# design.net
KiCad netlist of a schematic drawn in Altium Designer
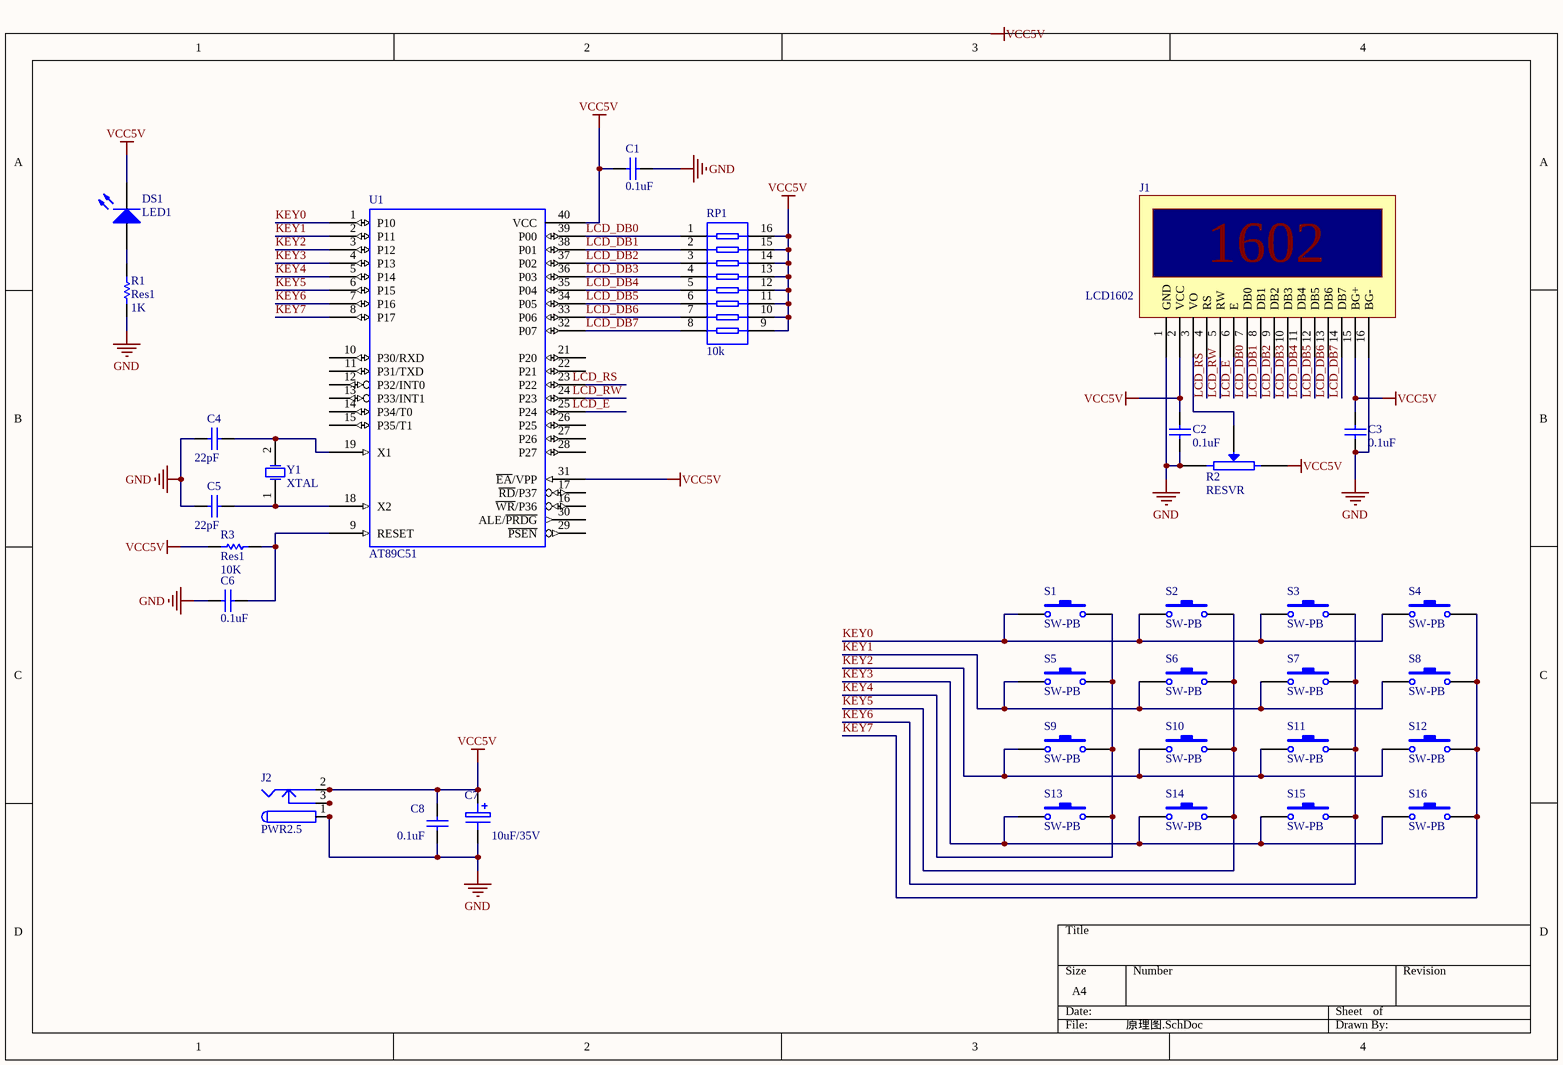
[diagram p0: 原理图.SchDoc]

(export (version "E")
  (design (tool "Eeschema 10.0.6"))
  (components
    (comp (ref "C1")
      (value "0.1uF")
      (footprint "RAD-0.3")
      (description "Capacitor")
      (fields (field (name "Comment") "Cap") (field (name "PUBLISHER") "Altium Limited"))
      (libsource (lib "Miscellaneous Devices") (part "Cap"))
    )
    (comp (ref "C2")
      (value "0.1uF")
      (footprint "RAD-0.3")
      (description "Capacitor")
      (fields (field (name "Comment") "Cap") (field (name "PUBLISHER") "Altium Limited"))
      (libsource (lib "Miscellaneous Devices") (part "Cap"))
    )
    (comp (ref "C3")
      (value "0.1uF")
      (footprint "RAD-0.3")
      (description "Capacitor")
      (fields (field (name "Comment") "Cap") (field (name "PUBLISHER") "Altium Limited"))
      (libsource (lib "Miscellaneous Devices") (part "Cap"))
    )
    (comp (ref "C4")
      (value "22pF")
      (footprint "RAD-0.3")
      (description "Capacitor")
      (fields (field (name "Comment") "Cap") (field (name "PUBLISHER") "Altium Limited"))
      (libsource (lib "Miscellaneous Devices") (part "Cap"))
    )
    (comp (ref "C5")
      (value "22pF")
      (footprint "RAD-0.3")
      (description "Capacitor")
      (fields (field (name "Comment") "Cap") (field (name "PUBLISHER") "Altium Limited"))
      (libsource (lib "Miscellaneous Devices") (part "Cap"))
    )
    (comp (ref "C6")
      (value "0.1uF")
      (footprint "RAD-0.3")
      (description "Capacitor")
      (fields (field (name "Comment") "Cap") (field (name "PUBLISHER") "Altium Limited"))
      (libsource (lib "Miscellaneous Devices") (part "Cap"))
    )
    (comp (ref "C7") (value "10uF/35V") (footprint "RB.1/.2") (libsource (lib "电容") (part "EC")))
    (comp (ref "C8")
      (value "0.1uF")
      (footprint "RAD-0.3")
      (description "Capacitor")
      (fields (field (name "Comment") "Cap") (field (name "PUBLISHER") "Altium Limited"))
      (libsource (lib "Miscellaneous Devices") (part "Cap"))
    )
    (comp (ref "DS1")
      (value "LED1")
      (footprint "LED-1")
      (description "Typical RED GaAs LED")
      (fields (field (name "PUBLISHER") "Altium Limited"))
      (libsource (lib "Miscellaneous Devices") (part "LED1"))
    )
    (comp (ref "J1") (value "LCD1602") (libsource (lib "常用元件库") (part "LCD1602")))
    (comp (ref "J2")
      (value "PWR2.5")
      (footprint "KLD-0202")
      (description "Low Voltage Power Supply Connector")
      (fields (field (name "PUBLISHER") "Altium Limited"))
      (libsource (lib "Miscellaneous Connectors") (part "PWR2.5"))
    )
    (comp (ref "R1")
      (value "Res1")
      (footprint "AXIAL-0.3")
      (description "Resistor")
      (fields (field (name "ALTIUM_VALUE") "1K") (field (name "PUBLISHER") "Altium Limited"))
      (libsource (lib "Miscellaneous Devices") (part "Res1"))
    )
    (comp (ref "R2")
      (value "RESVR")
      (footprint "VR")
      (description "Potentiometer")
      (libsource (lib "电阻") (part "RESVR"))
    )
    (comp (ref "R3")
      (value "Res1")
      (footprint "AXIAL-0.3")
      (description "Resistor")
      (fields (field (name "ALTIUM_VALUE") "10K") (field (name "PUBLISHER") "Altium Limited"))
      (libsource (lib "Miscellaneous Devices") (part "Res1"))
    )
    (comp (ref "RP1") (value "10k") (footprint "DIP16") (libsource (lib "电阻") (part "RESPACK4")))
    (comp (ref "S1")
      (value "SW-PB")
      (footprint "SPST-2")
      (description "Switch")
      (fields (field (name "PUBLISHER") "Altium Limited"))
      (libsource (lib "Miscellaneous Devices") (part "SW-PB"))
    )
    (comp (ref "S2")
      (value "SW-PB")
      (footprint "SPST-2")
      (description "Switch")
      (fields (field (name "PUBLISHER") "Altium Limited"))
      (libsource (lib "Miscellaneous Devices") (part "SW-PB"))
    )
    (comp (ref "S3")
      (value "SW-PB")
      (footprint "SPST-2")
      (description "Switch")
      (fields (field (name "PUBLISHER") "Altium Limited"))
      (libsource (lib "Miscellaneous Devices") (part "SW-PB"))
    )
    (comp (ref "S4")
      (value "SW-PB")
      (footprint "SPST-2")
      (description "Switch")
      (fields (field (name "PUBLISHER") "Altium Limited"))
      (libsource (lib "Miscellaneous Devices") (part "SW-PB"))
    )
    (comp (ref "S5")
      (value "SW-PB")
      (footprint "SPST-2")
      (description "Switch")
      (fields (field (name "PUBLISHER") "Altium Limited"))
      (libsource (lib "Miscellaneous Devices") (part "SW-PB"))
    )
    (comp (ref "S6")
      (value "SW-PB")
      (footprint "SPST-2")
      (description "Switch")
      (fields (field (name "PUBLISHER") "Altium Limited"))
      (libsource (lib "Miscellaneous Devices") (part "SW-PB"))
    )
    (comp (ref "S7")
      (value "SW-PB")
      (footprint "SPST-2")
      (description "Switch")
      (fields (field (name "PUBLISHER") "Altium Limited"))
      (libsource (lib "Miscellaneous Devices") (part "SW-PB"))
    )
    (comp (ref "S8")
      (value "SW-PB")
      (footprint "SPST-2")
      (description "Switch")
      (fields (field (name "PUBLISHER") "Altium Limited"))
      (libsource (lib "Miscellaneous Devices") (part "SW-PB"))
    )
    (comp (ref "S9")
      (value "SW-PB")
      (footprint "SPST-2")
      (description "Switch")
      (fields (field (name "PUBLISHER") "Altium Limited"))
      (libsource (lib "Miscellaneous Devices") (part "SW-PB"))
    )
    (comp (ref "S10")
      (value "SW-PB")
      (footprint "SPST-2")
      (description "Switch")
      (fields (field (name "PUBLISHER") "Altium Limited"))
      (libsource (lib "Miscellaneous Devices") (part "SW-PB"))
    )
    (comp (ref "S11")
      (value "SW-PB")
      (footprint "SPST-2")
      (description "Switch")
      (fields (field (name "PUBLISHER") "Altium Limited"))
      (libsource (lib "Miscellaneous Devices") (part "SW-PB"))
    )
    (comp (ref "S12")
      (value "SW-PB")
      (footprint "SPST-2")
      (description "Switch")
      (fields (field (name "PUBLISHER") "Altium Limited"))
      (libsource (lib "Miscellaneous Devices") (part "SW-PB"))
    )
    (comp (ref "S13")
      (value "SW-PB")
      (footprint "SPST-2")
      (description "Switch")
      (fields (field (name "PUBLISHER") "Altium Limited"))
      (libsource (lib "Miscellaneous Devices") (part "SW-PB"))
    )
    (comp (ref "S14")
      (value "SW-PB")
      (footprint "SPST-2")
      (description "Switch")
      (fields (field (name "PUBLISHER") "Altium Limited"))
      (libsource (lib "Miscellaneous Devices") (part "SW-PB"))
    )
    (comp (ref "S15")
      (value "SW-PB")
      (footprint "SPST-2")
      (description "Switch")
      (fields (field (name "PUBLISHER") "Altium Limited"))
      (libsource (lib "Miscellaneous Devices") (part "SW-PB"))
    )
    (comp (ref "S16")
      (value "SW-PB")
      (footprint "SPST-2")
      (description "Switch")
      (fields (field (name "PUBLISHER") "Altium Limited"))
      (libsource (lib "Miscellaneous Devices") (part "SW-PB"))
    )
    (comp (ref "U1") (value "AT89C51") (footprint "DIP-40") (libsource (lib "单片机及相关") (part "AT89C51")))
    (comp (ref "Y1")
      (value "XTAL")
      (footprint "BCY-W2/D3.1")
      (description "Crystal Oscillator")
      (fields (field (name "PUBLISHER") "Altium Limited"))
      (libsource (lib "Miscellaneous Devices") (part "XTAL"))
    )
  )
  (nets
    (net (code "1") (name "/KEY0") (class "Default")
      (node (ref "S1") (pin "1") (pinfunction "1_1") (pintype "passive"))
      (node (ref "S2") (pin "1") (pinfunction "1_1") (pintype "passive"))
      (node (ref "S3") (pin "1") (pinfunction "1_1") (pintype "passive"))
      (node (ref "S4") (pin "1") (pinfunction "1_1") (pintype "passive"))
      (node (ref "U1") (pin "1") (pinfunction "P10_1") (pintype "bidirectional"))
    )
    (net (code "2") (name "/KEY1") (class "Default")
      (node (ref "S5") (pin "1") (pinfunction "1_1") (pintype "passive"))
      (node (ref "S6") (pin "1") (pinfunction "1_1") (pintype "passive"))
      (node (ref "S7") (pin "1") (pinfunction "1_1") (pintype "passive"))
      (node (ref "S8") (pin "1") (pinfunction "1_1") (pintype "passive"))
      (node (ref "U1") (pin "2") (pinfunction "P11_2") (pintype "bidirectional"))
    )
    (net (code "3") (name "/KEY2") (class "Default")
      (node (ref "S10") (pin "1") (pinfunction "1_1") (pintype "passive"))
      (node (ref "S11") (pin "1") (pinfunction "1_1") (pintype "passive"))
      (node (ref "S12") (pin "1") (pinfunction "1_1") (pintype "passive"))
      (node (ref "S9") (pin "1") (pinfunction "1_1") (pintype "passive"))
      (node (ref "U1") (pin "3") (pinfunction "P12_3") (pintype "bidirectional"))
    )
    (net (code "4") (name "/KEY3") (class "Default")
      (node (ref "S13") (pin "1") (pinfunction "1_1") (pintype "passive"))
      (node (ref "S14") (pin "1") (pinfunction "1_1") (pintype "passive"))
      (node (ref "S15") (pin "1") (pinfunction "1_1") (pintype "passive"))
      (node (ref "S16") (pin "1") (pinfunction "1_1") (pintype "passive"))
      (node (ref "U1") (pin "4") (pinfunction "P13_4") (pintype "bidirectional"))
    )
    (net (code "5") (name "/KEY4") (class "Default")
      (node (ref "S1") (pin "2") (pinfunction "2_2") (pintype "passive"))
      (node (ref "S13") (pin "2") (pinfunction "2_2") (pintype "passive"))
      (node (ref "S5") (pin "2") (pinfunction "2_2") (pintype "passive"))
      (node (ref "S9") (pin "2") (pinfunction "2_2") (pintype "passive"))
      (node (ref "U1") (pin "5") (pinfunction "P14_5") (pintype "bidirectional"))
    )
    (net (code "6") (name "/KEY5") (class "Default")
      (node (ref "S10") (pin "2") (pinfunction "2_2") (pintype "passive"))
      (node (ref "S14") (pin "2") (pinfunction "2_2") (pintype "passive"))
      (node (ref "S2") (pin "2") (pinfunction "2_2") (pintype "passive"))
      (node (ref "S6") (pin "2") (pinfunction "2_2") (pintype "passive"))
      (node (ref "U1") (pin "6") (pinfunction "P15_6") (pintype "bidirectional"))
    )
    (net (code "7") (name "/KEY6") (class "Default")
      (node (ref "S11") (pin "2") (pinfunction "2_2") (pintype "passive"))
      (node (ref "S15") (pin "2") (pinfunction "2_2") (pintype "passive"))
      (node (ref "S3") (pin "2") (pinfunction "2_2") (pintype "passive"))
      (node (ref "S7") (pin "2") (pinfunction "2_2") (pintype "passive"))
      (node (ref "U1") (pin "7") (pinfunction "P16_7") (pintype "bidirectional"))
    )
    (net (code "8") (name "/KEY7") (class "Default")
      (node (ref "S12") (pin "2") (pinfunction "2_2") (pintype "passive"))
      (node (ref "S16") (pin "2") (pinfunction "2_2") (pintype "passive"))
      (node (ref "S4") (pin "2") (pinfunction "2_2") (pintype "passive"))
      (node (ref "S8") (pin "2") (pinfunction "2_2") (pintype "passive"))
      (node (ref "U1") (pin "8") (pinfunction "P17_8") (pintype "bidirectional"))
    )
    (net (code "9") (name "/LCD_DB0") (class "Default")
      (node (ref "J1") (pin "7") (pinfunction "DB0_7") (pintype "passive"))
      (node (ref "RP1") (pin "1") (pinfunction "1_1") (pintype "passive"))
      (node (ref "U1") (pin "39") (pinfunction "P00_39") (pintype "bidirectional"))
    )
    (net (code "10") (name "/LCD_DB1") (class "Default")
      (node (ref "J1") (pin "8") (pinfunction "DB1_8") (pintype "passive"))
      (node (ref "RP1") (pin "2") (pinfunction "2_2") (pintype "passive"))
      (node (ref "U1") (pin "38") (pinfunction "P01_38") (pintype "bidirectional"))
    )
    (net (code "11") (name "/LCD_DB2") (class "Default")
      (node (ref "J1") (pin "9") (pinfunction "DB2_9") (pintype "passive"))
      (node (ref "RP1") (pin "3") (pinfunction "3_3") (pintype "passive"))
      (node (ref "U1") (pin "37") (pinfunction "P02_37") (pintype "bidirectional"))
    )
    (net (code "12") (name "/LCD_DB3") (class "Default")
      (node (ref "J1") (pin "10") (pinfunction "DB3_10") (pintype "passive"))
      (node (ref "RP1") (pin "4") (pinfunction "4_4") (pintype "passive"))
      (node (ref "U1") (pin "36") (pinfunction "P03_36") (pintype "bidirectional"))
    )
    (net (code "13") (name "/LCD_DB4") (class "Default")
      (node (ref "J1") (pin "11") (pinfunction "DB4_11") (pintype "passive"))
      (node (ref "RP1") (pin "5") (pinfunction "5_5") (pintype "passive"))
      (node (ref "U1") (pin "35") (pinfunction "P04_35") (pintype "bidirectional"))
    )
    (net (code "14") (name "/LCD_DB5") (class "Default")
      (node (ref "J1") (pin "12") (pinfunction "DB5_12") (pintype "passive"))
      (node (ref "RP1") (pin "6") (pinfunction "6_6") (pintype "passive"))
      (node (ref "U1") (pin "34") (pinfunction "P05_34") (pintype "bidirectional"))
    )
    (net (code "15") (name "/LCD_DB6") (class "Default")
      (node (ref "J1") (pin "13") (pinfunction "DB6_13") (pintype "passive"))
      (node (ref "RP1") (pin "7") (pinfunction "7_7") (pintype "passive"))
      (node (ref "U1") (pin "33") (pinfunction "P06_33") (pintype "bidirectional"))
    )
    (net (code "16") (name "/LCD_DB7") (class "Default")
      (node (ref "J1") (pin "14") (pinfunction "DB7_14") (pintype "passive"))
      (node (ref "RP1") (pin "8") (pinfunction "8_8") (pintype "passive"))
      (node (ref "U1") (pin "32") (pinfunction "P07_32") (pintype "bidirectional"))
    )
    (net (code "17") (name "/LCD_E") (class "Default")
      (node (ref "J1") (pin "6") (pinfunction "E_6") (pintype "passive"))
    )
    (net (code "18") (name "/LCD_RS") (class "Default")
      (node (ref "J1") (pin "4") (pinfunction "RS_4") (pintype "passive"))
    )
    (net (code "19") (name "/LCD_RW") (class "Default")
      (node (ref "J1") (pin "5") (pinfunction "RW_5") (pintype "passive"))
    )
    (net (code "20") (name "GND") (class "Default")
      (node (ref "C1") (pin "1") (pinfunction "1_1") (pintype "passive"))
      (node (ref "C2") (pin "2") (pinfunction "2_2") (pintype "passive"))
      (node (ref "C3") (pin "2") (pinfunction "2_2") (pintype "passive"))
      (node (ref "C4") (pin "1") (pinfunction "1_1") (pintype "passive"))
      (node (ref "C5") (pin "1") (pinfunction "1_1") (pintype "passive"))
      (node (ref "C6") (pin "2") (pinfunction "2_2") (pintype "passive"))
      (node (ref "C7") (pin "2") (pinfunction "E_2") (pintype "passive"))
      (node (ref "C8") (pin "2") (pinfunction "2_2") (pintype "passive"))
      (node (ref "J1") (pin "1") (pinfunction "GND_1") (pintype "passive"))
      (node (ref "J1") (pin "16") (pinfunction "BG-_16") (pintype "passive"))
      (node (ref "J2") (pin "1") (pinfunction "1_1") (pintype "power_in"))
      (node (ref "J2") (pin "1A") (pinfunction "1A_1A") (pintype "power_in"))
      (node (ref "J2") (pin "1B") (pinfunction "1B_1B") (pintype "power_in"))
      (node (ref "R1") (pin "1") (pinfunction "1_1") (pintype "passive"))
      (node (ref "R2") (pin "1") (pinfunction "1_1") (pintype "passive"))
      (node (ref "U1") (pin "20") (pinfunction "GND_20") (pintype "power_in"))
    )
    (net (code "21") (name "Net-(DS1-A)") (class "Default")
      (node (ref "DS1") (pin "1") (pinfunction "A_1") (pintype "passive"))
      (node (ref "R1") (pin "2") (pinfunction "2_2") (pintype "passive"))
    )
    (net (code "22") (name "Net-(J1-VO)") (class "Default")
      (node (ref "J1") (pin "3") (pinfunction "VO_3") (pintype "passive"))
      (node (ref "R2") (pin "3") (pinfunction "W_3") (pintype "passive"))
    )
    (net (code "23") (name "Net-(J2-Pad3)") (class "Default")
      (node (ref "J2") (pin "3") (pinfunction "3_3") (pintype "power_in"))
      (node (ref "J2") (pin "3A") (pinfunction "3A_3A") (pintype "power_in"))
      (node (ref "J2") (pin "3B") (pinfunction "3B_3B") (pintype "power_in"))
    )
    (net (code "24") (name "Net-(U1-RESET)") (class "Default")
      (node (ref "C6") (pin "1") (pinfunction "1_1") (pintype "passive"))
      (node (ref "R3") (pin "2") (pinfunction "2_2") (pintype "passive"))
      (node (ref "U1") (pin "9") (pinfunction "RESET_9") (pintype "input"))
    )
    (net (code "25") (name "Net-(U1-X1)") (class "Default")
      (node (ref "C4") (pin "2") (pinfunction "2_2") (pintype "passive"))
      (node (ref "U1") (pin "19") (pinfunction "X1_19") (pintype "input"))
      (node (ref "Y1") (pin "2") (pinfunction "OSC2_2") (pintype "passive"))
    )
    (net (code "26") (name "Net-(U1-X2)") (class "Default")
      (node (ref "C5") (pin "2") (pinfunction "2_2") (pintype "passive"))
      (node (ref "U1") (pin "18") (pinfunction "X2_18") (pintype "input"))
      (node (ref "Y1") (pin "1") (pinfunction "OSC1_1") (pintype "passive"))
    )
    (net (code "27") (name "VCC") (class "Default")
      (node (ref "U1") (pin "40") (pinfunction "VCC_40") (pintype "power_in"))
    )
    (net (code "28") (name "VCC5V") (class "Default")
      (node (ref "C1") (pin "2") (pinfunction "2_2") (pintype "passive"))
      (node (ref "C2") (pin "1") (pinfunction "1_1") (pintype "passive"))
      (node (ref "C3") (pin "1") (pinfunction "1_1") (pintype "passive"))
      (node (ref "C7") (pin "1") (pinfunction "1_1") (pintype "passive"))
      (node (ref "C8") (pin "1") (pinfunction "1_1") (pintype "passive"))
      (node (ref "DS1") (pin "2") (pinfunction "K_2") (pintype "passive"))
      (node (ref "J1") (pin "15") (pinfunction "BG+_15") (pintype "passive"))
      (node (ref "J1") (pin "2") (pinfunction "VCC_2") (pintype "passive"))
      (node (ref "J2") (pin "2") (pinfunction "2_2") (pintype "power_in"))
      (node (ref "J2") (pin "2A") (pinfunction "2A_2A") (pintype "power_in"))
      (node (ref "J2") (pin "2B") (pinfunction "2B_2B") (pintype "power_in"))
      (node (ref "R2") (pin "2") (pinfunction "2_2") (pintype "passive"))
      (node (ref "R3") (pin "1") (pinfunction "1_1") (pintype "passive"))
      (node (ref "RP1") (pin "10") (pinfunction "10_10") (pintype "passive"))
      (node (ref "RP1") (pin "11") (pinfunction "11_11") (pintype "passive"))
      (node (ref "RP1") (pin "12") (pinfunction "12_12") (pintype "passive"))
      (node (ref "RP1") (pin "13") (pinfunction "13_13") (pintype "passive"))
      (node (ref "RP1") (pin "14") (pinfunction "14_14") (pintype "passive"))
      (node (ref "RP1") (pin "15") (pinfunction "15_15") (pintype "passive"))
      (node (ref "RP1") (pin "16") (pinfunction "16_16") (pintype "passive"))
      (node (ref "RP1") (pin "9") (pinfunction "9_9") (pintype "passive"))
      (node (ref "U1") (pin "31") (pinfunction "~{EA}/VPP_31") (pintype "input"))
      (node (ref "U1") (pin "40") (pinfunction "VCC_40") (pintype "passive"))
    )
    (net (code "29") (name "unconnected-(U1-ALE{slash}~{PRDG}-Pad30)") (class "Default")
      (node (ref "U1") (pin "30") (pinfunction "ALE/~{PRDG}_30") (pintype "output"))
    )
    (net (code "30") (name "unconnected-(U1-P20-Pad21)") (class "Default")
      (node (ref "U1") (pin "21") (pinfunction "P20_21") (pintype "bidirectional"))
    )
    (net (code "31") (name "unconnected-(U1-P21-Pad22)") (class "Default")
      (node (ref "U1") (pin "22") (pinfunction "P21_22") (pintype "bidirectional"))
    )
    (net (code "32") (name "unconnected-(U1-P22-Pad23)") (class "Default")
      (node (ref "U1") (pin "23") (pinfunction "P22_23") (pintype "bidirectional"))
    )
    (net (code "33") (name "unconnected-(U1-P23-Pad24)") (class "Default")
      (node (ref "U1") (pin "24") (pinfunction "P23_24") (pintype "bidirectional"))
    )
    (net (code "34") (name "unconnected-(U1-P24-Pad25)") (class "Default")
      (node (ref "U1") (pin "25") (pinfunction "P24_25") (pintype "bidirectional"))
    )
    (net (code "35") (name "unconnected-(U1-P25-Pad26)") (class "Default")
      (node (ref "U1") (pin "26") (pinfunction "P25_26") (pintype "bidirectional"))
    )
    (net (code "36") (name "unconnected-(U1-P26-Pad27)") (class "Default")
      (node (ref "U1") (pin "27") (pinfunction "P26_27") (pintype "bidirectional"))
    )
    (net (code "37") (name "unconnected-(U1-P27-Pad28)") (class "Default")
      (node (ref "U1") (pin "28") (pinfunction "P27_28") (pintype "bidirectional"))
    )
    (net (code "38") (name "unconnected-(U1-P30{slash}RXD-Pad10)") (class "Default")
      (node (ref "U1") (pin "10") (pinfunction "P30/RXD_10") (pintype "bidirectional"))
    )
    (net (code "39") (name "unconnected-(U1-P31{slash}TXD-Pad11)") (class "Default")
      (node (ref "U1") (pin "11") (pinfunction "P31/TXD_11") (pintype "bidirectional"))
    )
    (net (code "40") (name "unconnected-(U1-P32{slash}INT0-Pad12)") (class "Default")
      (node (ref "U1") (pin "12") (pinfunction "P32/INT0_12") (pintype "bidirectional"))
    )
    (net (code "41") (name "unconnected-(U1-P33{slash}INT1-Pad13)") (class "Default")
      (node (ref "U1") (pin "13") (pinfunction "P33/INT1_13") (pintype "bidirectional"))
    )
    (net (code "42") (name "unconnected-(U1-P34{slash}T0-Pad14)") (class "Default")
      (node (ref "U1") (pin "14") (pinfunction "P34/T0_14") (pintype "bidirectional"))
    )
    (net (code "43") (name "unconnected-(U1-P35{slash}T1-Pad15)") (class "Default")
      (node (ref "U1") (pin "15") (pinfunction "P35/T1_15") (pintype "bidirectional"))
    )
    (net (code "44") (name "unconnected-(U1-~{PSEN}-Pad29)") (class "Default")
      (node (ref "U1") (pin "29") (pinfunction "~{PSEN}_29") (pintype "output"))
    )
    (net (code "45") (name "unconnected-(U1-~{RD}{slash}P37-Pad17)") (class "Default")
      (node (ref "U1") (pin "17") (pinfunction "~{RD}/P37_17") (pintype "bidirectional"))
    )
    (net (code "46") (name "unconnected-(U1-~{WR}{slash}P36-Pad16)") (class "Default")
      (node (ref "U1") (pin "16") (pinfunction "~{WR}/P36_16") (pintype "bidirectional"))
    )
  )
)
